# Power.net
KiCad netlist of a schematic drawn in Altium Designer
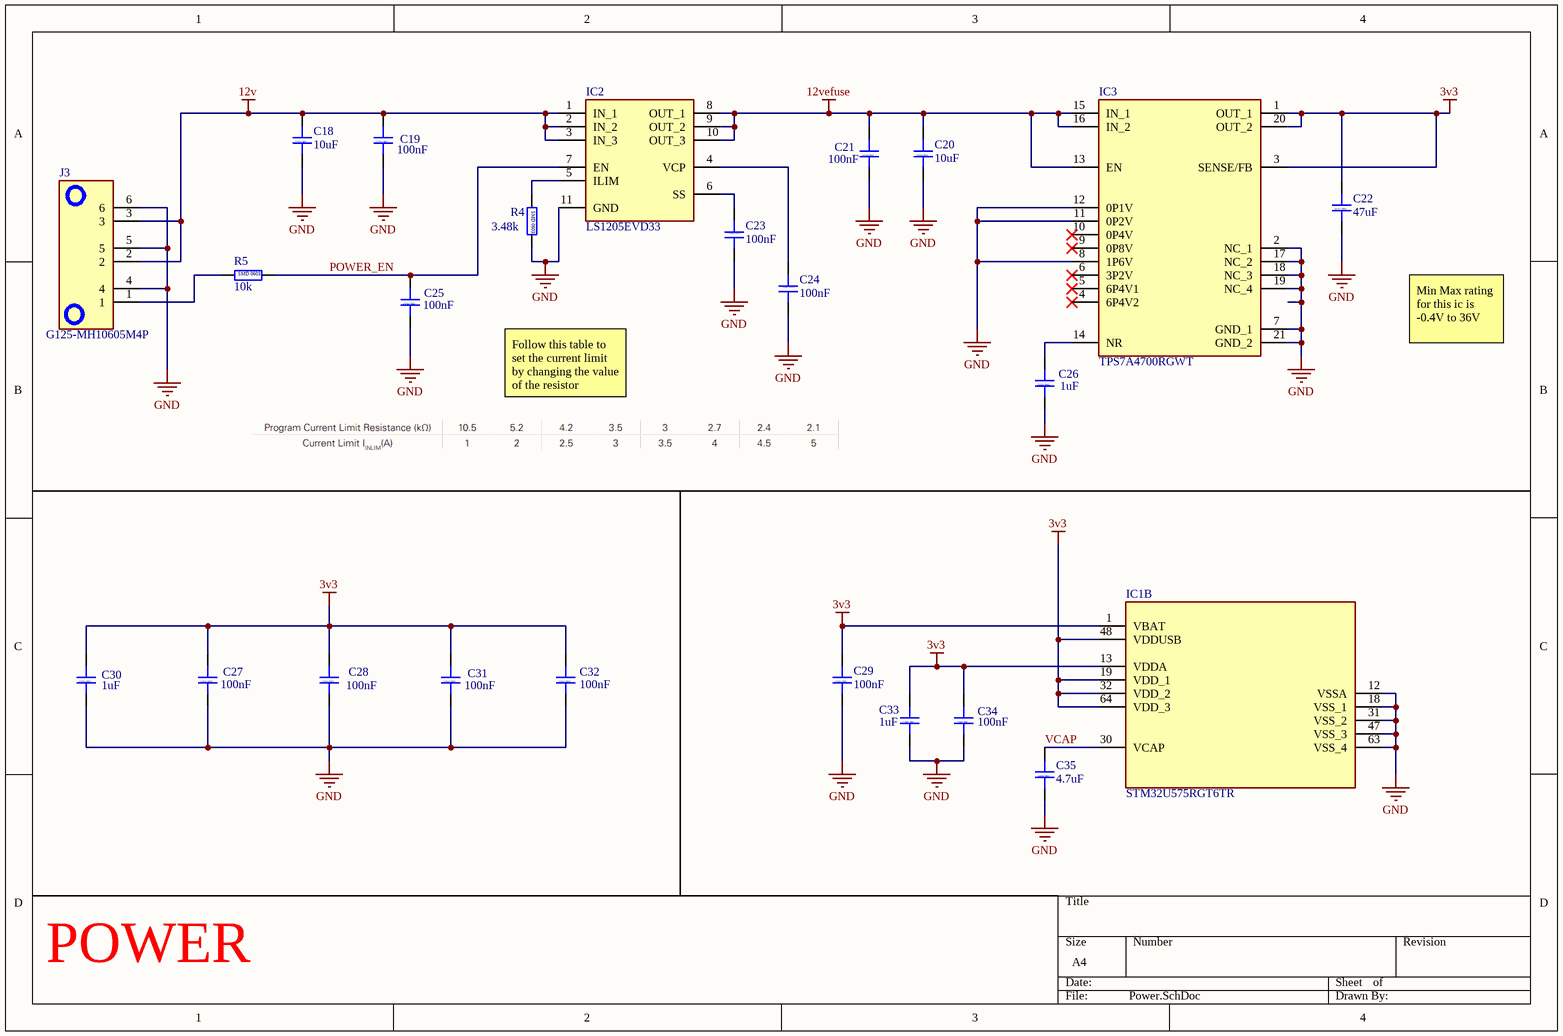
[diagram p0:  Power.SchDoc]

(export (version "E")
  (design (tool "Eeschema 10.0.6"))
  (components
    (comp (ref "C18")
      (value "10uF")
      (footprint "CAP_0805")
      (description "Capacitor SMD 0805 RATED")
      (libsource (lib "STeRG-Passives-Standard") (part "Capacitor-SMD-0805"))
    )
    (comp (ref "C19")
      (value "100nF")
      (footprint "CAP_0603")
      (description "Capacitor SMD 0603 RATED")
      (libsource (lib "STeRG-Passives-Standard") (part "Capacitor-SMD-0603"))
    )
    (comp (ref "C20")
      (value "10uF")
      (footprint "CAP_0805")
      (description "Capacitor SMD 0805 RATED")
      (libsource (lib "STeRG-Passives-Standard") (part "Capacitor-SMD-0805"))
    )
    (comp (ref "C21")
      (value "100nF")
      (footprint "CAP_0603")
      (description "Capacitor SMD 0603 RATED")
      (libsource (lib "STeRG-Passives-Standard") (part "Capacitor-SMD-0603"))
    )
    (comp (ref "C22")
      (value "47uF")
      (footprint "CAP_1210")
      (description "Capacitor SMD 1210 RATED")
      (libsource (lib "STeRG-Passives-Standard") (part "Capacitor-SMD-1210"))
    )
    (comp (ref "C23")
      (value "100nF")
      (footprint "CAP_0603")
      (description "Capacitor SMD 0603 RATED")
      (libsource (lib "STeRG-Passives-Standard") (part "Capacitor-SMD-0603"))
    )
    (comp (ref "C24")
      (value "100nF")
      (footprint "CAP_0603")
      (description "Capacitor SMD 0603 RATED")
      (libsource (lib "STeRG-Passives-Standard") (part "Capacitor-SMD-0603"))
    )
    (comp (ref "C25")
      (value "100nF")
      (footprint "CAP_0603")
      (description "Capacitor SMD 0603 RATED")
      (libsource (lib "STeRG-Passives-Standard") (part "Capacitor-SMD-0603"))
    )
    (comp (ref "C26")
      (value "1uF")
      (footprint "CAP_0603")
      (description "Capacitor SMD 0603 RATED")
      (libsource (lib "STeRG-Passives-Standard") (part "Capacitor-SMD-0603"))
    )
    (comp (ref "C27")
      (value "100nF")
      (footprint "CAP_0603")
      (description "Capacitor SMD 0603 RATED")
      (libsource (lib "STeRG-Passives-Standard") (part "Capacitor-SMD-0603"))
    )
    (comp (ref "C28")
      (value "100nF")
      (footprint "CAP_0603")
      (description "Capacitor SMD 0603 RATED")
      (libsource (lib "STeRG-Passives-Standard") (part "Capacitor-SMD-0603"))
    )
    (comp (ref "C29")
      (value "100nF")
      (footprint "CAP_0603")
      (description "Capacitor SMD 0603 RATED")
      (libsource (lib "STeRG-Passives-Standard") (part "Capacitor-SMD-0603"))
    )
    (comp (ref "C30")
      (value "1uF")
      (footprint "CAP_0603")
      (description "Capacitor SMD 0603 RATED")
      (libsource (lib "STeRG-Passives-Standard") (part "Capacitor-SMD-0603"))
    )
    (comp (ref "C31")
      (value "100nF")
      (footprint "CAP_0603")
      (description "Capacitor SMD 0603 RATED")
      (libsource (lib "STeRG-Passives-Standard") (part "Capacitor-SMD-0603"))
    )
    (comp (ref "C32")
      (value "100nF")
      (footprint "CAP_0603")
      (description "Capacitor SMD 0603 RATED")
      (libsource (lib "STeRG-Passives-Standard") (part "Capacitor-SMD-0603"))
    )
    (comp (ref "C33")
      (value "1uF")
      (footprint "CAP_0603")
      (description "Capacitor SMD 0603 RATED")
      (libsource (lib "STeRG-Passives-Standard") (part "Capacitor-SMD-0603"))
    )
    (comp (ref "C34")
      (value "100nF")
      (footprint "CAP_0603")
      (description "Capacitor SMD 0603 RATED")
      (libsource (lib "STeRG-Passives-Standard") (part "Capacitor-SMD-0603"))
    )
    (comp (ref "C35")
      (value "4.7uF")
      (footprint "CAP_0603")
      (description "Capacitor SMD 0603 RATED")
      (libsource (lib "STeRG-Passives-Standard") (part "Capacitor-SMD-0603"))
    )
    (comp (ref "IC1")
      (value "STM32U575RGT6TR")
      (footprint "QFP50P1200X1200X160-64N")
      (description "Integrated Circuit")
      (fields (field (name "MOUSER PART NUMBER") "511-STM32U575RGT6TR"))
      (libsource (lib "STeRG-ICs-Standard") (part "STM32U575RGT6TR"))
    )
    (comp (ref "IC2")
      (value "LS1205EVD33")
      (footprint "SamacSys:LS1205EVD33")
      (description "Integrated Circuit")
      (fields (field (name "MOUSER PART NUMBER") "576-LS1205EVD33"))
      (libsource (lib "SamacSys") (part "LS1205EVD33"))
    )
    (comp (ref "IC3")
      (value "TPS7A4700RGWT")
      (footprint "SamacSys:QFN65P500X500X100-21N-D")
      (description "Integrated Circuit")
      (fields
        (field (name "MANUFACTURER_PART_NUMBER") "TPS7A4700RGWR")
        (field (name "MOUSER PART NUMBER") "595-TPS7A4700RGWR")
      )
      (libsource (lib "SamacSys") (part "TPS7A4700RGWR"))
    )
    (comp (ref "J3")
      (value "G125-MH10605M4P")
      (footprint "G125-MH10605M4P_1")
      (description "Connector")
      (fields (field (name "MOUSER PART NUMBER") "855-G125MH1065M4PM4P"))
      (libsource (lib "STeRG-Passives-Standard") (part "G125-MH10605M4P"))
    )
    (comp (ref "R4")
      (value "3.48k")
      (footprint "RES_0603")
      (description "Resistor SMD 0603 RATED")
      (libsource (lib "STeRG-Passives-Standard") (part "Resistor-SMD-0603"))
    )
    (comp (ref "R5")
      (value "10k")
      (footprint "RES_0603")
      (description "Resistor SMD 0603 RATED")
      (libsource (lib "STeRG-Passives-Standard") (part "Resistor-SMD-0603"))
    )
  )
  (nets
    (net (code "1") (name "/POWER_EN") (class "Default")
      (node (ref "C25") (pin "2") (pinfunction "2_2") (pintype "passive"))
      (node (ref "IC2") (pin "7") (pinfunction "EN_7") (pintype "passive"))
      (node (ref "R5") (pin "2") (pinfunction "2_2") (pintype "passive"))
    )
    (net (code "2") (name "/VCAP") (class "Default")
      (node (ref "C35") (pin "2") (pinfunction "2_2") (pintype "passive"))
      (node (ref "IC1") (pin "30") (pinfunction "VCAP_30") (pintype "passive"))
    )
    (net (code "3") (name "3v3") (class "Default")
      (node (ref "C22") (pin "2") (pinfunction "2_2") (pintype "passive"))
      (node (ref "C27") (pin "2") (pinfunction "2_2") (pintype "passive"))
      (node (ref "C28") (pin "2") (pinfunction "2_2") (pintype "passive"))
      (node (ref "C29") (pin "2") (pinfunction "2_2") (pintype "passive"))
      (node (ref "C30") (pin "2") (pinfunction "2_2") (pintype "passive"))
      (node (ref "C31") (pin "2") (pinfunction "2_2") (pintype "passive"))
      (node (ref "C32") (pin "2") (pinfunction "2_2") (pintype "passive"))
      (node (ref "C33") (pin "2") (pinfunction "2_2") (pintype "passive"))
      (node (ref "C34") (pin "2") (pinfunction "2_2") (pintype "passive"))
      (node (ref "IC1") (pin "1") (pinfunction "VBAT_1") (pintype "passive"))
      (node (ref "IC1") (pin "13") (pinfunction "VDDA_13") (pintype "passive"))
      (node (ref "IC1") (pin "19") (pinfunction "VDD_1_19") (pintype "passive"))
      (node (ref "IC1") (pin "32") (pinfunction "VDD_2_32") (pintype "passive"))
      (node (ref "IC1") (pin "48") (pinfunction "VDDUSB_48") (pintype "passive"))
      (node (ref "IC1") (pin "64") (pinfunction "VDD_3_64") (pintype "passive"))
      (node (ref "IC3") (pin "1") (pinfunction "OUT_1_1") (pintype "passive"))
      (node (ref "IC3") (pin "20") (pinfunction "OUT_2_20") (pintype "passive"))
      (node (ref "IC3") (pin "3") (pinfunction "SENSE/FB_3") (pintype "passive"))
    )
    (net (code "4") (name "12v") (class "Default")
      (node (ref "C18") (pin "2") (pinfunction "2_2") (pintype "passive"))
      (node (ref "C19") (pin "2") (pinfunction "2_2") (pintype "passive"))
      (node (ref "IC2") (pin "1") (pinfunction "IN_1_1") (pintype "passive"))
      (node (ref "IC2") (pin "2") (pinfunction "IN_2_2") (pintype "passive"))
      (node (ref "IC2") (pin "3") (pinfunction "IN_3_3") (pintype "passive"))
      (node (ref "J3") (pin "2") (pinfunction "2_2") (pintype "passive"))
      (node (ref "J3") (pin "3") (pinfunction "3_3") (pintype "passive"))
    )
    (net (code "5") (name "12vefuse") (class "Default")
      (node (ref "C20") (pin "2") (pinfunction "2_2") (pintype "passive"))
      (node (ref "C21") (pin "2") (pinfunction "2_2") (pintype "passive"))
      (node (ref "IC2") (pin "10") (pinfunction "OUT_3_10") (pintype "passive"))
      (node (ref "IC2") (pin "8") (pinfunction "OUT_1_8") (pintype "passive"))
      (node (ref "IC2") (pin "9") (pinfunction "OUT_2_9") (pintype "passive"))
      (node (ref "IC3") (pin "13") (pinfunction "EN_13") (pintype "passive"))
      (node (ref "IC3") (pin "15") (pinfunction "IN_1_15") (pintype "passive"))
      (node (ref "IC3") (pin "16") (pinfunction "IN_2_16") (pintype "passive"))
    )
    (net (code "6") (name "GND") (class "Default")
      (node (ref "C18") (pin "1") (pinfunction "1_1") (pintype "passive"))
      (node (ref "C19") (pin "1") (pinfunction "1_1") (pintype "passive"))
      (node (ref "C20") (pin "1") (pinfunction "1_1") (pintype "passive"))
      (node (ref "C21") (pin "1") (pinfunction "1_1") (pintype "passive"))
      (node (ref "C22") (pin "1") (pinfunction "1_1") (pintype "passive"))
      (node (ref "C23") (pin "2") (pinfunction "2_2") (pintype "passive"))
      (node (ref "C24") (pin "2") (pinfunction "2_2") (pintype "passive"))
      (node (ref "C25") (pin "1") (pinfunction "1_1") (pintype "passive"))
      (node (ref "C26") (pin "1") (pinfunction "1_1") (pintype "passive"))
      (node (ref "C27") (pin "1") (pinfunction "1_1") (pintype "passive"))
      (node (ref "C28") (pin "1") (pinfunction "1_1") (pintype "passive"))
      (node (ref "C29") (pin "1") (pinfunction "1_1") (pintype "passive"))
      (node (ref "C30") (pin "1") (pinfunction "1_1") (pintype "passive"))
      (node (ref "C31") (pin "1") (pinfunction "1_1") (pintype "passive"))
      (node (ref "C32") (pin "1") (pinfunction "1_1") (pintype "passive"))
      (node (ref "C33") (pin "1") (pinfunction "1_1") (pintype "passive"))
      (node (ref "C34") (pin "1") (pinfunction "1_1") (pintype "passive"))
      (node (ref "C35") (pin "1") (pinfunction "1_1") (pintype "passive"))
      (node (ref "IC1") (pin "12") (pinfunction "VSSA_12") (pintype "passive"))
      (node (ref "IC1") (pin "18") (pinfunction "VSS_1_18") (pintype "passive"))
      (node (ref "IC1") (pin "31") (pinfunction "VSS_2_31") (pintype "passive"))
      (node (ref "IC1") (pin "47") (pinfunction "VSS_3_47") (pintype "passive"))
      (node (ref "IC1") (pin "63") (pinfunction "VSS_4_63") (pintype "passive"))
      (node (ref "IC2") (pin "11") (pinfunction "GND_11") (pintype "passive"))
      (node (ref "IC3") (pin "11") (pinfunction "0P2V_11") (pintype "passive"))
      (node (ref "IC3") (pin "12") (pinfunction "0P1V_12") (pintype "passive"))
      (node (ref "IC3") (pin "17") (pinfunction "NC_2_17") (pintype "passive"))
      (node (ref "IC3") (pin "18") (pinfunction "NC_3_18") (pintype "passive"))
      (node (ref "IC3") (pin "19") (pinfunction "NC_4_19") (pintype "passive"))
      (node (ref "IC3") (pin "2") (pinfunction "NC_1_2") (pintype "passive"))
      (node (ref "IC3") (pin "21") (pinfunction "GND_2_21") (pintype "passive"))
      (node (ref "IC3") (pin "7") (pinfunction "GND_1_7") (pintype "passive"))
      (node (ref "IC3") (pin "8") (pinfunction "1P6V_8") (pintype "passive"))
      (node (ref "J3") (pin "4") (pinfunction "4_4") (pintype "passive"))
      (node (ref "J3") (pin "5") (pinfunction "5_5") (pintype "passive"))
      (node (ref "J3") (pin "6") (pinfunction "6_6") (pintype "passive"))
      (node (ref "R4") (pin "2") (pinfunction "2_2") (pintype "passive"))
    )
    (net (code "7") (name "Net-(IC2-ILIM)") (class "Default")
      (node (ref "IC2") (pin "5") (pinfunction "ILIM_5") (pintype "passive"))
      (node (ref "R4") (pin "1") (pinfunction "1_1") (pintype "passive"))
    )
    (net (code "8") (name "Net-(IC2-SS)") (class "Default")
      (node (ref "C23") (pin "1") (pinfunction "1_1") (pintype "passive"))
      (node (ref "IC2") (pin "6") (pinfunction "SS_6") (pintype "passive"))
    )
    (net (code "9") (name "Net-(IC2-VCP)") (class "Default")
      (node (ref "C24") (pin "1") (pinfunction "1_1") (pintype "passive"))
      (node (ref "IC2") (pin "4") (pinfunction "VCP_4") (pintype "passive"))
    )
    (net (code "10") (name "Net-(IC3-NR)") (class "Default")
      (node (ref "C26") (pin "2") (pinfunction "2_2") (pintype "passive"))
      (node (ref "IC3") (pin "14") (pinfunction "NR_14") (pintype "passive"))
    )
    (net (code "11") (name "Net-(J3-Pad1)") (class "Default")
      (node (ref "J3") (pin "1") (pinfunction "1_1") (pintype "passive"))
      (node (ref "R5") (pin "1") (pinfunction "1_1") (pintype "passive"))
    )
    (net (code "12") (name "unconnected-(IC3-0P4V-Pad10)") (class "Default")
      (node (ref "IC3") (pin "10") (pinfunction "0P4V_10") (pintype "passive+no_connect"))
    )
    (net (code "13") (name "unconnected-(IC3-0P8V-Pad9)") (class "Default")
      (node (ref "IC3") (pin "9") (pinfunction "0P8V_9") (pintype "passive+no_connect"))
    )
    (net (code "14") (name "unconnected-(IC3-3P2V-Pad6)") (class "Default")
      (node (ref "IC3") (pin "6") (pinfunction "3P2V_6") (pintype "passive+no_connect"))
    )
    (net (code "15") (name "unconnected-(IC3-6P4V1-Pad5)") (class "Default")
      (node (ref "IC3") (pin "5") (pinfunction "6P4V1_5") (pintype "passive+no_connect"))
    )
    (net (code "16") (name "unconnected-(IC3-6P4V2-Pad4)") (class "Default")
      (node (ref "IC3") (pin "4") (pinfunction "6P4V2_4") (pintype "passive+no_connect"))
    )
  )
)
